# fbri.net
KiCad netlist of a schematic drawn in EAGLE
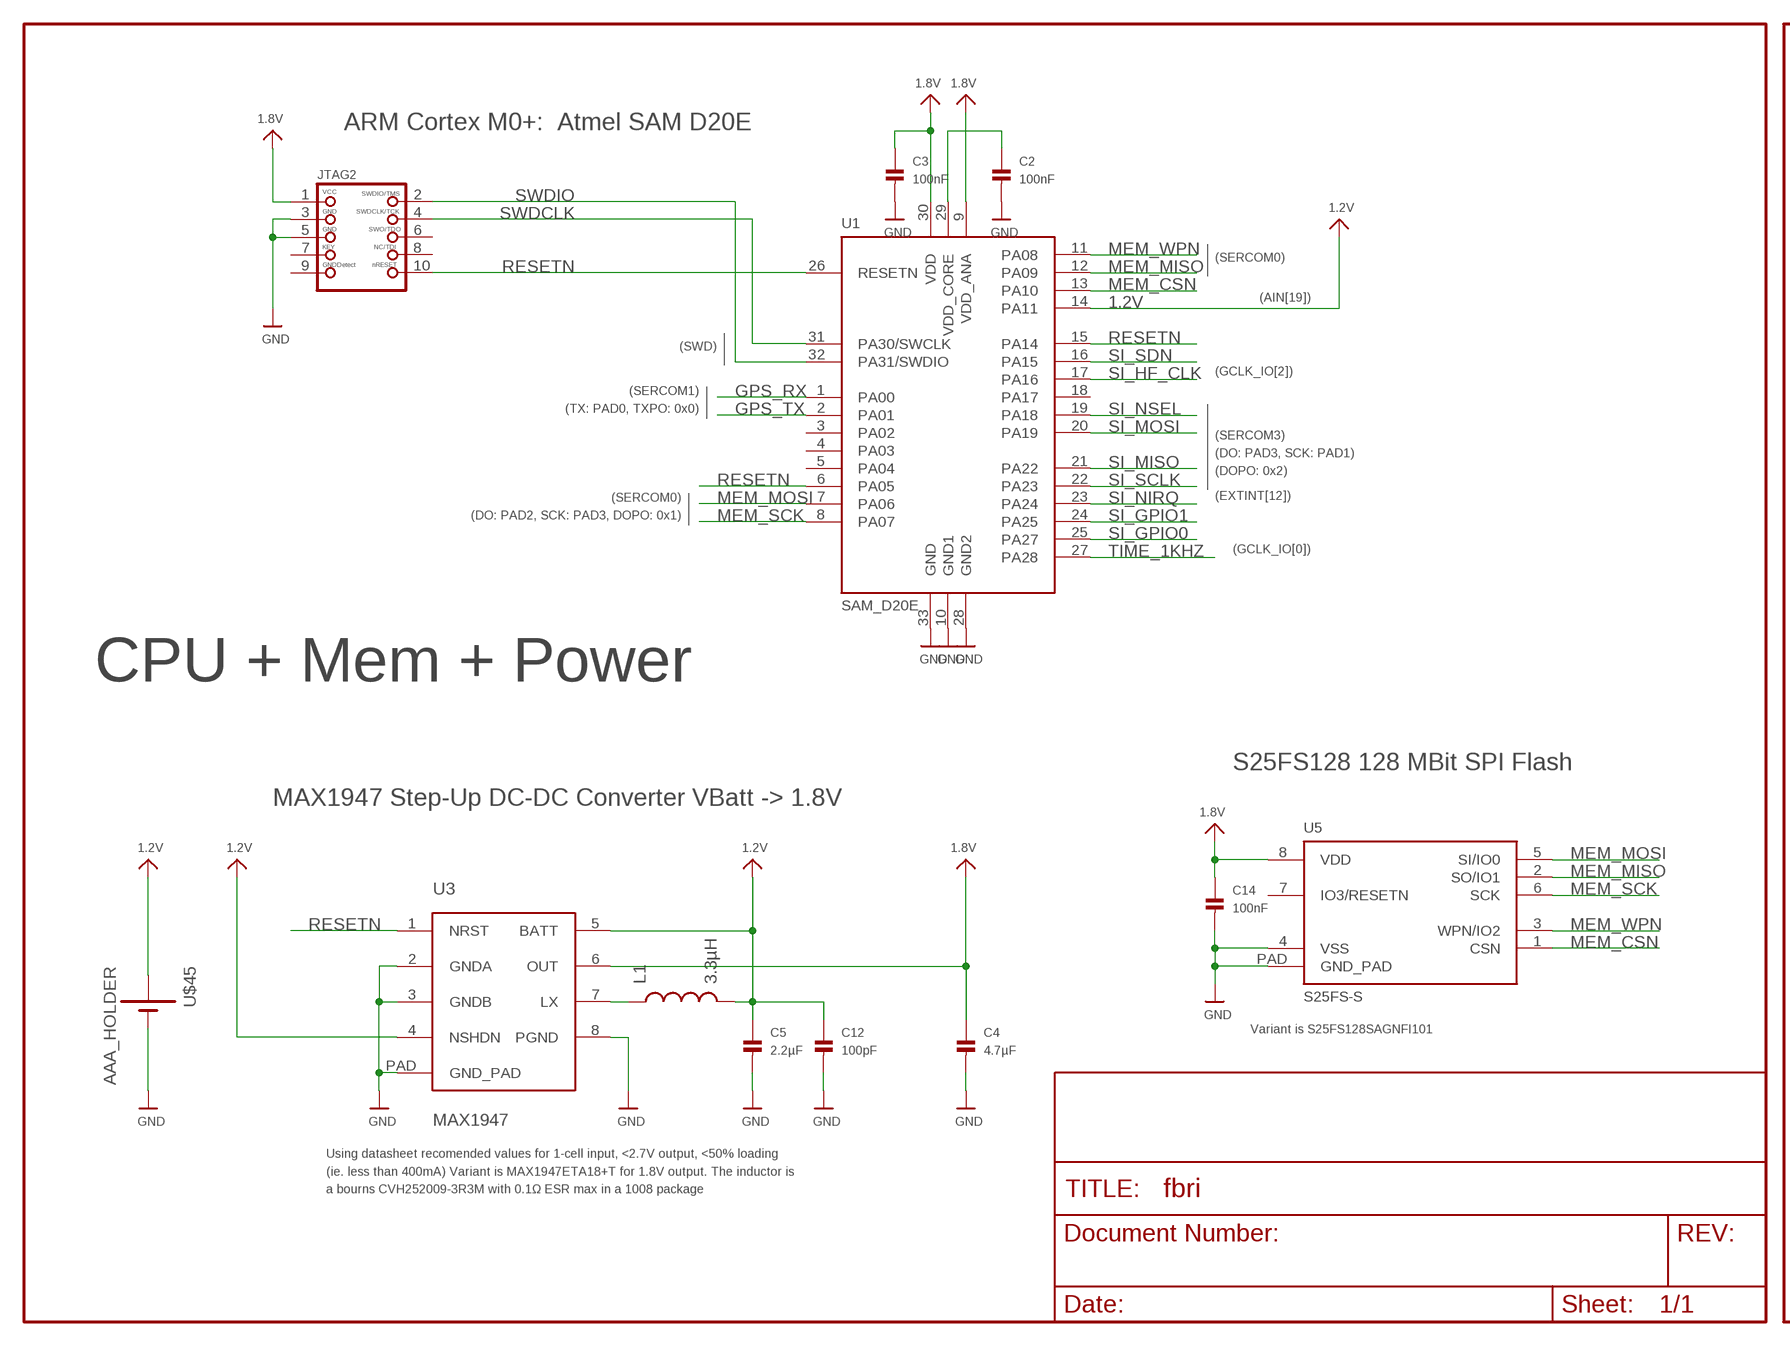
[diagram p0: schematic, sheet 1, part 1 of 2]
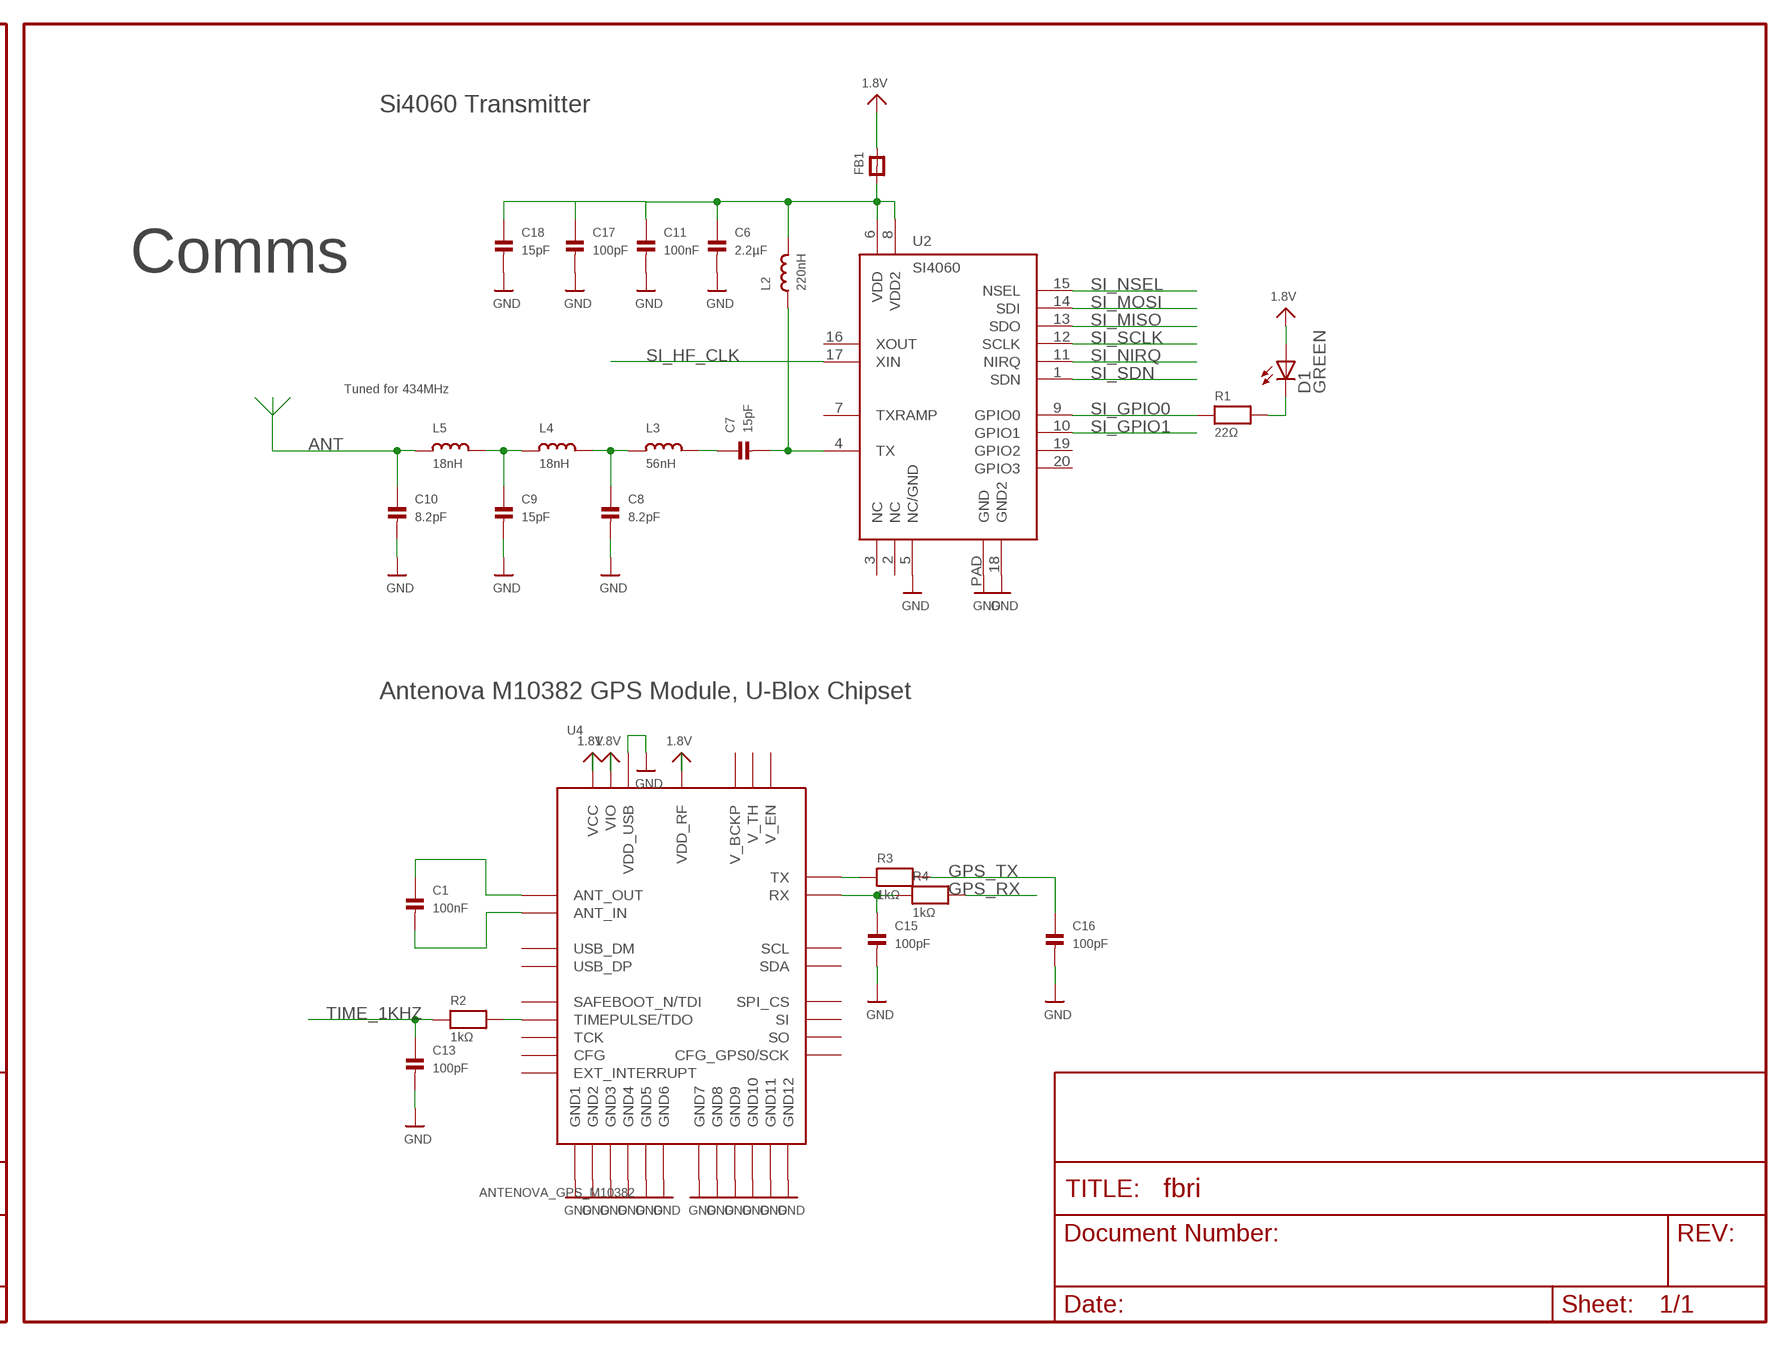
[diagram p1: schematic, sheet 1, part 2 of 2]

(export (version "E")
  (design (tool "Eeschema 10.0.6"))
  (components
    (comp (ref "C1")
      (value "100nF")
      (footprint "eagle-import:_0402")
      (libsource (lib "eagle-import") (part "CAP_CERAMIC_0402"))
    )
    (comp (ref "C2")
      (value "100nF")
      (footprint "eagle-import:_0402")
      (libsource (lib "eagle-import") (part "CAP_CERAMIC_0402"))
    )
    (comp (ref "C3")
      (value "100nF")
      (footprint "eagle-import:_0402")
      (libsource (lib "eagle-import") (part "CAP_CERAMIC_0402"))
    )
    (comp (ref "C4")
      (value "4.7µF")
      (footprint "eagle-import:_0402")
      (libsource (lib "eagle-import") (part "CAP_CERAMIC_0402"))
    )
    (comp (ref "C5")
      (value "2.2µF")
      (footprint "eagle-import:_0402")
      (libsource (lib "eagle-import") (part "CAP_CERAMIC_0402"))
    )
    (comp (ref "C6")
      (value "2.2µF")
      (footprint "eagle-import:_0402")
      (libsource (lib "eagle-import") (part "CAP_CERAMIC_0402"))
    )
    (comp (ref "C7")
      (value "15pF")
      (footprint "eagle-import:_0402")
      (libsource (lib "eagle-import") (part "CAP_CERAMIC_0402"))
    )
    (comp (ref "C8")
      (value "8.2pF")
      (footprint "eagle-import:_0402")
      (libsource (lib "eagle-import") (part "CAP_CERAMIC_0402"))
    )
    (comp (ref "C9")
      (value "15pF")
      (footprint "eagle-import:_0402")
      (libsource (lib "eagle-import") (part "CAP_CERAMIC_0402"))
    )
    (comp (ref "C10")
      (value "8.2pF")
      (footprint "eagle-import:_0402")
      (libsource (lib "eagle-import") (part "CAP_CERAMIC_0402"))
    )
    (comp (ref "C11")
      (value "100nF")
      (footprint "eagle-import:_0402")
      (libsource (lib "eagle-import") (part "CAP_CERAMIC_0402"))
    )
    (comp (ref "C12")
      (value "100pF")
      (footprint "eagle-import:_0402")
      (libsource (lib "eagle-import") (part "CAP_CERAMIC_0402"))
    )
    (comp (ref "C13")
      (value "100pF")
      (footprint "eagle-import:_0402")
      (libsource (lib "eagle-import") (part "CAP_CERAMIC_0402"))
    )
    (comp (ref "C14")
      (value "100nF")
      (footprint "eagle-import:_0402")
      (libsource (lib "eagle-import") (part "CAP_CERAMIC_0402"))
    )
    (comp (ref "C15")
      (value "100pF")
      (footprint "eagle-import:_0402")
      (libsource (lib "eagle-import") (part "CAP_CERAMIC_0402"))
    )
    (comp (ref "C16")
      (value "100pF")
      (footprint "eagle-import:_0402")
      (libsource (lib "eagle-import") (part "CAP_CERAMIC_0402"))
    )
    (comp (ref "C17")
      (value "100pF")
      (footprint "eagle-import:_0402")
      (libsource (lib "eagle-import") (part "CAP_CERAMIC_0402"))
    )
    (comp (ref "C18")
      (value "15pF")
      (footprint "eagle-import:_0402")
      (libsource (lib "eagle-import") (part "CAP_CERAMIC_0402"))
    )
    (comp (ref "D1")
      (value "GREEN")
      (footprint "eagle-import:CHIPLED_0603")
      (libsource (lib "eagle-import") (part "LEDCHIPLED_0603"))
    )
    (comp (ref "FB1")
      (value "FERRITE_0402")
      (footprint "eagle-import:_0402")
      (libsource (lib "eagle-import") (part "FERRITE_0402"))
    )
    (comp (ref "JTAG2")
      (value "JTAG-CORTEXM3SMT")
      (footprint "eagle-import:2X05_1.27MM_SMT")
      (libsource (lib "eagle-import") (part "JTAG-CORTEXM3SMT"))
    )
    (comp (ref "L1")
      (value "3.3µH")
      (footprint "eagle-import:1007")
      (libsource (lib "eagle-import") (part "INDUCTOR1007"))
    )
    (comp (ref "L2")
      (value "220nH")
      (footprint "eagle-import:_0402")
      (libsource (lib "eagle-import") (part "INDUCTOR_0402"))
    )
    (comp (ref "L3")
      (value "56nH")
      (footprint "eagle-import:_0402")
      (libsource (lib "eagle-import") (part "INDUCTOR_0402"))
    )
    (comp (ref "L4")
      (value "18nH")
      (footprint "eagle-import:_0402")
      (libsource (lib "eagle-import") (part "INDUCTOR_0402"))
    )
    (comp (ref "L5")
      (value "18nH")
      (footprint "eagle-import:_0402")
      (libsource (lib "eagle-import") (part "INDUCTOR_0402"))
    )
    (comp (ref "R1")
      (value "22Ω")
      (footprint "eagle-import:_0402")
      (libsource (lib "eagle-import") (part "RESISTOR_0402"))
    )
    (comp (ref "R2")
      (value "1kΩ")
      (footprint "eagle-import:_0402")
      (libsource (lib "eagle-import") (part "RESISTOR_0402"))
    )
    (comp (ref "R3")
      (value "1kΩ")
      (footprint "eagle-import:_0402")
      (libsource (lib "eagle-import") (part "RESISTOR_0402"))
    )
    (comp (ref "R4")
      (value "1kΩ")
      (footprint "eagle-import:_0402")
      (libsource (lib "eagle-import") (part "RESISTOR_0402"))
    )
    (comp (ref "U$45")
      (value "AAA_HOLDER")
      (footprint "eagle-import:AAA")
      (libsource (lib "eagle-import") (part "AAA_HOLDER"))
    )
    (comp (ref "U1")
      (value "SAM_D20E")
      (footprint "eagle-import:QFN32_5MM")
      (libsource (lib "eagle-import") (part "SAM_D20E"))
    )
    (comp (ref "U2")
      (value "SI4060")
      (footprint "eagle-import:QFN20")
      (libsource (lib "eagle-import") (part "SI4060"))
    )
    (comp (ref "U3")
      (value "MAX1947")
      (footprint "eagle-import:TDFN8")
      (libsource (lib "eagle-import") (part "MAX1947"))
    )
    (comp (ref "U4")
      (value "ANTENOVA_GPS_M10382")
      (footprint "eagle-import:ANTENOVA_GPS_M10382")
      (libsource (lib "eagle-import") (part "ANTENOVA_GPS_M10382"))
    )
    (comp (ref "U5")
      (value "S25FS-S")
      (footprint "eagle-import:WSON8")
      (libsource (lib "eagle-import") (part "S25FS-S"))
    )
  )
  (nets
    (net (code "1") (name "/ANT") (class "Default")
      (node (ref "C10") (pin "1") (pinfunction "P$1_1") (pintype "passive"))
      (node (ref "L5") (pin "1") (pinfunction "1_1") (pintype "passive"))
    )
    (net (code "2") (name "/GPS_RX") (class "Default")
      (node (ref "R4") (pin "2") (pinfunction "2_2") (pintype "passive"))
      (node (ref "U1") (pin "1") (pinfunction "PA00_1") (pintype "bidirectional"))
    )
    (net (code "3") (name "/GPS_TX") (class "Default")
      (node (ref "C16") (pin "1") (pinfunction "P$1_1") (pintype "passive"))
      (node (ref "R3") (pin "2") (pinfunction "2_2") (pintype "passive"))
      (node (ref "U1") (pin "2") (pinfunction "PA01_2") (pintype "bidirectional"))
    )
    (net (code "4") (name "/MEM_CSN") (class "Default")
      (node (ref "U1") (pin "13") (pinfunction "PA10_13") (pintype "bidirectional"))
      (node (ref "U5") (pin "1") (pinfunction "CSN_1") (pintype "input"))
    )
    (net (code "5") (name "/MEM_MISO") (class "Default")
      (node (ref "U1") (pin "12") (pinfunction "PA09_12") (pintype "bidirectional"))
      (node (ref "U5") (pin "2") (pinfunction "SO/IO1_2") (pintype "output"))
    )
    (net (code "6") (name "/MEM_MOSI") (class "Default")
      (node (ref "U1") (pin "7") (pinfunction "PA06_7") (pintype "bidirectional"))
      (node (ref "U5") (pin "5") (pinfunction "SI/IO0_5") (pintype "bidirectional"))
    )
    (net (code "7") (name "/MEM_SCK") (class "Default")
      (node (ref "U1") (pin "8") (pinfunction "PA07_8") (pintype "bidirectional"))
      (node (ref "U5") (pin "6") (pinfunction "SCK_6") (pintype "input"))
    )
    (net (code "8") (name "/MEM_WPN") (class "Default")
      (node (ref "U1") (pin "11") (pinfunction "PA08_11") (pintype "bidirectional"))
      (node (ref "U5") (pin "3") (pinfunction "WPN/IO2_3") (pintype "output"))
    )
    (net (code "9") (name "/RESETN") (class "Default")
      (node (ref "JTAG2") (pin "10") (pinfunction "10_10") (pintype "passive"))
      (node (ref "U1") (pin "15") (pinfunction "PA14_15") (pintype "bidirectional"))
      (node (ref "U1") (pin "26") (pinfunction "RESETN_26") (pintype "input"))
      (node (ref "U1") (pin "6") (pinfunction "PA05_6") (pintype "bidirectional"))
      (node (ref "U3") (pin "1") (pinfunction "NRST_1") (pintype "bidirectional"))
    )
    (net (code "10") (name "/SI_GPIO0") (class "Default")
      (node (ref "R1") (pin "1") (pinfunction "1_1") (pintype "passive"))
      (node (ref "U1") (pin "25") (pinfunction "PA27_25") (pintype "bidirectional"))
      (node (ref "U2") (pin "9") (pinfunction "GPIO0_9") (pintype "bidirectional"))
    )
    (net (code "11") (name "/SI_GPIO1") (class "Default")
      (node (ref "U1") (pin "24") (pinfunction "PA25_24") (pintype "bidirectional"))
      (node (ref "U2") (pin "10") (pinfunction "GPIO1_10") (pintype "bidirectional"))
    )
    (net (code "12") (name "/SI_HF_CLK") (class "Default")
      (node (ref "U1") (pin "17") (pinfunction "PA16_17") (pintype "bidirectional"))
      (node (ref "U2") (pin "17") (pinfunction "XIN_17") (pintype "input"))
    )
    (net (code "13") (name "/SI_MISO") (class "Default")
      (node (ref "U1") (pin "21") (pinfunction "PA22_21") (pintype "bidirectional"))
      (node (ref "U2") (pin "13") (pinfunction "SDO_13") (pintype "output"))
    )
    (net (code "14") (name "/SI_MOSI") (class "Default")
      (node (ref "U1") (pin "20") (pinfunction "PA19_20") (pintype "bidirectional"))
      (node (ref "U2") (pin "14") (pinfunction "SDI_14") (pintype "bidirectional"))
    )
    (net (code "15") (name "/SI_NIRQ") (class "Default")
      (node (ref "U1") (pin "23") (pinfunction "PA24_23") (pintype "bidirectional"))
      (node (ref "U2") (pin "11") (pinfunction "NIRQ_11") (pintype "output"))
    )
    (net (code "16") (name "/SI_NSEL") (class "Default")
      (node (ref "U1") (pin "19") (pinfunction "PA18_19") (pintype "bidirectional"))
      (node (ref "U2") (pin "15") (pinfunction "NSEL_15") (pintype "input"))
    )
    (net (code "17") (name "/SI_SCLK") (class "Default")
      (node (ref "U1") (pin "22") (pinfunction "PA23_22") (pintype "bidirectional"))
      (node (ref "U2") (pin "12") (pinfunction "SCLK_12") (pintype "input"))
    )
    (net (code "18") (name "/SI_SDN") (class "Default")
      (node (ref "U1") (pin "16") (pinfunction "PA15_16") (pintype "bidirectional"))
      (node (ref "U2") (pin "1") (pinfunction "SDN_1") (pintype "input"))
    )
    (net (code "19") (name "/SWDCLK") (class "Default")
      (node (ref "JTAG2") (pin "4") (pinfunction "4_4") (pintype "passive"))
      (node (ref "U1") (pin "31") (pinfunction "PA30/SWCLK_31") (pintype "bidirectional"))
    )
    (net (code "20") (name "/SWDIO") (class "Default")
      (node (ref "JTAG2") (pin "2") (pinfunction "2_2") (pintype "passive"))
      (node (ref "U1") (pin "32") (pinfunction "PA31/SWDIO_32") (pintype "bidirectional"))
    )
    (net (code "21") (name "/TIME_1KHZ") (class "Default")
      (node (ref "C13") (pin "1") (pinfunction "P$1_1") (pintype "passive"))
      (node (ref "R2") (pin "1") (pinfunction "1_1") (pintype "passive"))
      (node (ref "U1") (pin "27") (pinfunction "PA28_27") (pintype "bidirectional"))
    )
    (net (code "22") (name "1.2V") (class "Default")
      (node (ref "C12") (pin "1") (pinfunction "P$1_1") (pintype "passive"))
      (node (ref "C5") (pin "1") (pinfunction "P$1_1") (pintype "passive"))
      (node (ref "L1") (pin "2") (pinfunction "2_2") (pintype "passive"))
      (node (ref "U$45") (pin "+2") (pinfunction "+_+2") (pintype "power_in"))
      (node (ref "U1") (pin "14") (pinfunction "PA11_14") (pintype "bidirectional"))
      (node (ref "U3") (pin "4") (pinfunction "NSHDN_4") (pintype "bidirectional"))
      (node (ref "U3") (pin "5") (pinfunction "BATT_5") (pintype "bidirectional"))
    )
    (net (code "23") (name "1.8V") (class "Default")
      (node (ref "C14") (pin "1") (pinfunction "P$1_1") (pintype "passive"))
      (node (ref "C3") (pin "1") (pinfunction "P$1_1") (pintype "passive"))
      (node (ref "C4") (pin "1") (pinfunction "P$1_1") (pintype "passive"))
      (node (ref "D1") (pin "A") (pinfunction "A_A") (pintype "passive"))
      (node (ref "FB1") (pin "2") (pinfunction "P$2_2") (pintype "passive"))
      (node (ref "JTAG2") (pin "1") (pinfunction "1_1") (pintype "passive"))
      (node (ref "U1") (pin "30") (pinfunction "VDD_30") (pintype "power_in"))
      (node (ref "U1") (pin "9") (pinfunction "VDD_ANA_9") (pintype "power_in"))
      (node (ref "U3") (pin "6") (pinfunction "OUT_6") (pintype "bidirectional"))
      (node (ref "U4") (pin "25_VDD_RF") (pinfunction "VDD_RF_25_VDD_RF") (pintype "power_in"))
      (node (ref "U4") (pin "27_VCC") (pinfunction "VCC_27_VCC") (pintype "power_in"))
      (node (ref "U4") (pin "5_VIO") (pinfunction "VIO_5_VIO") (pintype "bidirectional"))
      (node (ref "U5") (pin "8") (pinfunction "VDD_8") (pintype "power_in"))
    )
    (net (code "24") (name "GND") (class "Default")
      (node (ref "C10") (pin "2") (pinfunction "P$2_2") (pintype "passive"))
      (node (ref "C11") (pin "2") (pinfunction "P$2_2") (pintype "passive"))
      (node (ref "C12") (pin "2") (pinfunction "P$2_2") (pintype "passive"))
      (node (ref "C13") (pin "2") (pinfunction "P$2_2") (pintype "passive"))
      (node (ref "C14") (pin "2") (pinfunction "P$2_2") (pintype "passive"))
      (node (ref "C15") (pin "2") (pinfunction "P$2_2") (pintype "passive"))
      (node (ref "C16") (pin "2") (pinfunction "P$2_2") (pintype "passive"))
      (node (ref "C17") (pin "2") (pinfunction "P$2_2") (pintype "passive"))
      (node (ref "C18") (pin "2") (pinfunction "P$2_2") (pintype "passive"))
      (node (ref "C2") (pin "2") (pinfunction "P$2_2") (pintype "passive"))
      (node (ref "C3") (pin "2") (pinfunction "P$2_2") (pintype "passive"))
      (node (ref "C4") (pin "2") (pinfunction "P$2_2") (pintype "passive"))
      (node (ref "C5") (pin "2") (pinfunction "P$2_2") (pintype "passive"))
      (node (ref "C6") (pin "2") (pinfunction "P$2_2") (pintype "passive"))
      (node (ref "C8") (pin "2") (pinfunction "P$2_2") (pintype "passive"))
      (node (ref "C9") (pin "2") (pinfunction "P$2_2") (pintype "passive"))
      (node (ref "JTAG2") (pin "3") (pinfunction "3_3") (pintype "passive"))
      (node (ref "JTAG2") (pin "5") (pinfunction "5_5") (pintype "passive"))
      (node (ref "U$45") (pin "-1") (pinfunction "-_-1") (pintype "power_in"))
      (node (ref "U$45") (pin "-2") (pinfunction "-_-2") (pintype "power_in"))
      (node (ref "U1") (pin "10") (pinfunction "GND1_10") (pintype "power_in"))
      (node (ref "U1") (pin "28") (pinfunction "GND2_28") (pintype "power_in"))
      (node (ref "U1") (pin "33") (pinfunction "GND_33") (pintype "power_in"))
      (node (ref "U2") (pin "18") (pinfunction "GND2_18") (pintype "power_in"))
      (node (ref "U2") (pin "5") (pinfunction "NC/GND_5") (pintype "bidirectional"))
      (node (ref "U2") (pin "PAD") (pinfunction "GND_PAD") (pintype "power_in"))
      (node (ref "U3") (pin "2") (pinfunction "GNDA_2") (pintype "bidirectional"))
      (node (ref "U3") (pin "3") (pinfunction "GNDB_3") (pintype "bidirectional"))
      (node (ref "U3") (pin "8") (pinfunction "PGND_8") (pintype "bidirectional"))
      (node (ref "U3") (pin "PAD") (pinfunction "GND_PAD_PAD") (pintype "bidirectional"))
      (node (ref "U4") (pin "14_GND") (pinfunction "GND3_14_GND") (pintype "power_in"))
      (node (ref "U4") (pin "17_GND") (pinfunction "GND4_17_GND") (pintype "power_in"))
      (node (ref "U4") (pin "21_GND") (pinfunction "GND5_21_GND") (pintype "bidirectional"))
      (node (ref "U4") (pin "24_GND") (pinfunction "GND6_24_GND") (pintype "bidirectional"))
      (node (ref "U4") (pin "26_GND") (pinfunction "GND7_26_GND") (pintype "power_in"))
      (node (ref "U4") (pin "28_GND") (pinfunction "GND8_28_GND") (pintype "power_in"))
      (node (ref "U4") (pin "2_GND") (pinfunction "GND1_2_GND") (pintype "power_in"))
      (node (ref "U4") (pin "32_VDD_USB") (pinfunction "VDD_USB_32_VDD_USB") (pintype "bidirectional"))
      (node (ref "U4") (pin "33_GND") (pinfunction "GND9_33_GND") (pintype "power_in"))
      (node (ref "U4") (pin "34_GND") (pinfunction "GND10_34_GND") (pintype "power_in"))
      (node (ref "U4") (pin "35_GND") (pinfunction "GND11_35_GND") (pintype "bidirectional"))
      (node (ref "U4") (pin "36_GND") (pinfunction "GND12_36_GND") (pintype "bidirectional"))
      (node (ref "U4") (pin "4_GND") (pinfunction "GND2_4_GND") (pintype "power_in"))
      (node (ref "U5") (pin "4") (pinfunction "VSS_4") (pintype "power_in"))
      (node (ref "U5") (pin "PAD") (pinfunction "GND_PAD_PAD") (pintype "power_in"))
    )
    (net (code "25") (name "Net-(C1-P$1)") (class "Default")
      (node (ref "C1") (pin "1") (pinfunction "P$1_1") (pintype "passive"))
      (node (ref "U4") (pin "3_ANT_OUT") (pinfunction "ANT_OUT_3_ANT_OUT") (pintype "output"))
    )
    (net (code "26") (name "Net-(C1-P$2)") (class "Default")
      (node (ref "C1") (pin "2") (pinfunction "P$2_2") (pintype "passive"))
      (node (ref "U4") (pin "1_ANT_IN") (pinfunction "ANT_IN_1_ANT_IN") (pintype "input"))
    )
    (net (code "27") (name "Net-(C2-P$1)") (class "Default")
      (node (ref "C2") (pin "1") (pinfunction "P$1_1") (pintype "passive"))
      (node (ref "U1") (pin "29") (pinfunction "VDD_CORE_29") (pintype "power_in"))
    )
    (net (code "28") (name "Net-(C7-P$1)") (class "Default")
      (node (ref "C7") (pin "1") (pinfunction "P$1_1") (pintype "passive"))
      (node (ref "L3") (pin "2") (pinfunction "2_2") (pintype "passive"))
    )
    (net (code "29") (name "Net-(C7-P$2)") (class "Default")
      (node (ref "C7") (pin "2") (pinfunction "P$2_2") (pintype "passive"))
      (node (ref "L2") (pin "1") (pinfunction "1_1") (pintype "passive"))
      (node (ref "U2") (pin "4") (pinfunction "TX_4") (pintype "output"))
    )
    (net (code "30") (name "Net-(C8-P$1)") (class "Default")
      (node (ref "C8") (pin "1") (pinfunction "P$1_1") (pintype "passive"))
      (node (ref "L3") (pin "1") (pinfunction "1_1") (pintype "passive"))
      (node (ref "L4") (pin "2") (pinfunction "2_2") (pintype "passive"))
    )
    (net (code "31") (name "Net-(C9-P$1)") (class "Default")
      (node (ref "C9") (pin "1") (pinfunction "P$1_1") (pintype "passive"))
      (node (ref "L4") (pin "1") (pinfunction "1_1") (pintype "passive"))
      (node (ref "L5") (pin "2") (pinfunction "2_2") (pintype "passive"))
    )
    (net (code "32") (name "Net-(C11-P$1)") (class "Default")
      (node (ref "C11") (pin "1") (pinfunction "P$1_1") (pintype "passive"))
      (node (ref "C17") (pin "1") (pinfunction "P$1_1") (pintype "passive"))
      (node (ref "C18") (pin "1") (pinfunction "P$1_1") (pintype "passive"))
      (node (ref "C6") (pin "1") (pinfunction "P$1_1") (pintype "passive"))
      (node (ref "FB1") (pin "1") (pinfunction "P$1_1") (pintype "passive"))
      (node (ref "L2") (pin "2") (pinfunction "2_2") (pintype "passive"))
      (node (ref "U2") (pin "6") (pinfunction "VDD_6") (pintype "power_in"))
      (node (ref "U2") (pin "8") (pinfunction "VDD2_8") (pintype "power_in"))
    )
    (net (code "33") (name "Net-(C15-P$1)") (class "Default")
      (node (ref "C15") (pin "1") (pinfunction "P$1_1") (pintype "passive"))
      (node (ref "R4") (pin "1") (pinfunction "1_1") (pintype "passive"))
      (node (ref "U4") (pin "13_RX") (pinfunction "RX_13_RX") (pintype "bidirectional"))
    )
    (net (code "34") (name "Net-(D1-PadC)") (class "Default")
      (node (ref "D1") (pin "C") (pinfunction "C_C") (pintype "passive"))
      (node (ref "R1") (pin "2") (pinfunction "2_2") (pintype "passive"))
    )
    (net (code "35") (name "Net-(U3-LX)") (class "Default")
      (node (ref "L1") (pin "1") (pinfunction "1_1") (pintype "passive"))
      (node (ref "U3") (pin "7") (pinfunction "LX_7") (pintype "bidirectional"))
    )
    (net (code "36") (name "Net-(U4-TIMEPULSE{slash}TDO)") (class "Default")
      (node (ref "R2") (pin "2") (pinfunction "2_2") (pintype "passive"))
      (node (ref "U4") (pin "23_TIMEPULSE/TDO") (pinfunction "TIMEPULSE/TDO_23_TIMEPULSE/TDO") (pintype "bidirectional"))
    )
    (net (code "37") (name "Net-(U4-TX)") (class "Default")
      (node (ref "R3") (pin "1") (pinfunction "1_1") (pintype "passive"))
      (node (ref "U4") (pin "11_TX") (pinfunction "TX_11_TX") (pintype "bidirectional"))
    )
    (net (code "38") (name "unconnected-(JTAG2-Pad6)") (class "Default")
      (node (ref "JTAG2") (pin "6") (pinfunction "6_6") (pintype "passive"))
    )
    (net (code "39") (name "unconnected-(JTAG2-Pad7)") (class "Default")
      (node (ref "JTAG2") (pin "7") (pinfunction "7_7") (pintype "passive"))
    )
    (net (code "40") (name "unconnected-(JTAG2-Pad8)") (class "Default")
      (node (ref "JTAG2") (pin "8") (pinfunction "8_8") (pintype "passive"))
    )
    (net (code "41") (name "unconnected-(JTAG2-Pad9)") (class "Default")
      (node (ref "JTAG2") (pin "9") (pinfunction "9_9") (pintype "passive"))
    )
    (net (code "42") (name "unconnected-(U1-PA02-Pad3)") (class "Default")
      (node (ref "U1") (pin "3") (pinfunction "PA02_3") (pintype "bidirectional"))
    )
    (net (code "43") (name "unconnected-(U1-PA03-Pad4)") (class "Default")
      (node (ref "U1") (pin "4") (pinfunction "PA03_4") (pintype "bidirectional"))
    )
    (net (code "44") (name "unconnected-(U1-PA04-Pad5)") (class "Default")
      (node (ref "U1") (pin "5") (pinfunction "PA04_5") (pintype "bidirectional"))
    )
    (net (code "45") (name "unconnected-(U1-PA17-Pad18)") (class "Default")
      (node (ref "U1") (pin "18") (pinfunction "PA17_18") (pintype "bidirectional"))
    )
    (net (code "46") (name "unconnected-(U2-GPIO2-Pad19)") (class "Default")
      (node (ref "U2") (pin "19") (pinfunction "GPIO2_19") (pintype "bidirectional"))
    )
    (net (code "47") (name "unconnected-(U2-GPIO3-Pad20)") (class "Default")
      (node (ref "U2") (pin "20") (pinfunction "GPIO3_20") (pintype "bidirectional"))
    )
    (net (code "48") (name "unconnected-(U2-NC-Pad2)") (class "Default")
      (node (ref "U2") (pin "2") (pinfunction "NC_2") (pintype "no_connect"))
    )
    (net (code "49") (name "unconnected-(U2-NC -Pad3)") (class "Default")
      (node (ref "U2") (pin "3") (pinfunction "NC _3") (pintype "no_connect"))
    )
    (net (code "50") (name "unconnected-(U2-TXRAMP-Pad7)") (class "Default")
      (node (ref "U2") (pin "7") (pinfunction "TXRAMP_7") (pintype "bidirectional"))
    )
    (net (code "51") (name "unconnected-(U2-XOUT-Pad16)") (class "Default")
      (node (ref "U2") (pin "16") (pinfunction "XOUT_16") (pintype "output"))
    )
    (net (code "52") (name "unconnected-(U4-CFG-Pad31_CFG)") (class "Default")
      (node (ref "U4") (pin "31_CFG") (pinfunction "CFG_31_CFG") (pintype "bidirectional"))
    )
    (net (code "53") (name "unconnected-(U4-CFG_GPS0{slash}SCK-Pad9_CFG_GPS0_SCK)") (class "Default")
      (node (ref "U4") (pin "9_CFG_GPS0_SCK") (pinfunction "CFG_GPS0/SCK_9_CFG_GPS0_SCK") (pintype "bidirectional"))
    )
    (net (code "54") (name "unconnected-(U4-EXT_INTERRUPT-Pad29_EXT_INTERRUPT)") (class "Default")
      (node (ref "U4") (pin "29_EXT_INTERRUPT") (pinfunction "EXT_INTERRUPT_29_EXT_INTERRUPT") (pintype "bidirectional"))
    )
    (net (code "55") (name "unconnected-(U4-SAFEBOOT_N{slash}TDI-Pad20_SAFEBOOT_N{slash}TDI)") (class "Default")
      (node (ref "U4") (pin "20_SAFEBOOT_N/TDI") (pinfunction "SAFEBOOT_N/TDI_20_SAFEBOOT_N/TDI") (pintype "bidirectional"))
    )
    (net (code "56") (name "unconnected-(U4-SCL-Pad19_SCL)") (class "Default")
      (node (ref "U4") (pin "19_SCL") (pinfunction "SCL_19_SCL") (pintype "bidirectional"))
    )
    (net (code "57") (name "unconnected-(U4-SDA-Pad18_SDA)") (class "Default")
      (node (ref "U4") (pin "18_SDA") (pinfunction "SDA_18_SDA") (pintype "bidirectional"))
    )
    (net (code "58") (name "unconnected-(U4-SI-Pad16_SI)") (class "Default")
      (node (ref "U4") (pin "16_SI") (pinfunction "SI_16_SI") (pintype "bidirectional"))
    )
    (net (code "59") (name "unconnected-(U4-SO-Pad8_SO)") (class "Default")
      (node (ref "U4") (pin "8_SO") (pinfunction "SO_8_SO") (pintype "bidirectional"))
    )
    (net (code "60") (name "unconnected-(U4-SPI_CS-Pad10_SPI_SELECT)") (class "Default")
      (node (ref "U4") (pin "10_SPI_SELECT") (pinfunction "SPI_CS_10_SPI_SELECT") (pintype "bidirectional"))
    )
    (net (code "61") (name "unconnected-(U4-TCK-Pad22_TCK)") (class "Default")
      (node (ref "U4") (pin "22_TCK") (pinfunction "TCK_22_TCK") (pintype "bidirectional"))
    )
    (net (code "62") (name "unconnected-(U4-USB_DM-Pad7_USB_DM)") (class "Default")
      (node (ref "U4") (pin "7_USB_DM") (pinfunction "USB_DM_7_USB_DM") (pintype "bidirectional"))
    )
    (net (code "63") (name "unconnected-(U4-USB_DP-Pad6_USB_DP)") (class "Default")
      (node (ref "U4") (pin "6_USB_DP") (pinfunction "USB_DP_6_USB_DP") (pintype "bidirectional"))
    )
    (net (code "64") (name "unconnected-(U4-V_BCKP-Pad15_V_BCKUP)") (class "Default")
      (node (ref "U4") (pin "15_V_BCKUP") (pinfunction "V_BCKP_15_V_BCKUP") (pintype "bidirectional"))
    )
    (net (code "65") (name "unconnected-(U4-V_EN-Pad30_V_EN)") (class "Default")
      (node (ref "U4") (pin "30_V_EN") (pinfunction "V_EN_30_V_EN") (pintype "bidirectional"))
    )
    (net (code "66") (name "unconnected-(U4-V_TH-Pad12_V_TH)") (class "Default")
      (node (ref "U4") (pin "12_V_TH") (pinfunction "V_TH_12_V_TH") (pintype "bidirectional"))
    )
    (net (code "67") (name "unconnected-(U5-IO3{slash}RESETN-Pad7)") (class "Default")
      (node (ref "U5") (pin "7") (pinfunction "IO3/RESETN_7") (pintype "output"))
    )
  )
)
